# UBC-Thunderbots_PCB_Power__power-v2_2_pc.net
KiCad netlist of a schematic drawn in Altium Designer
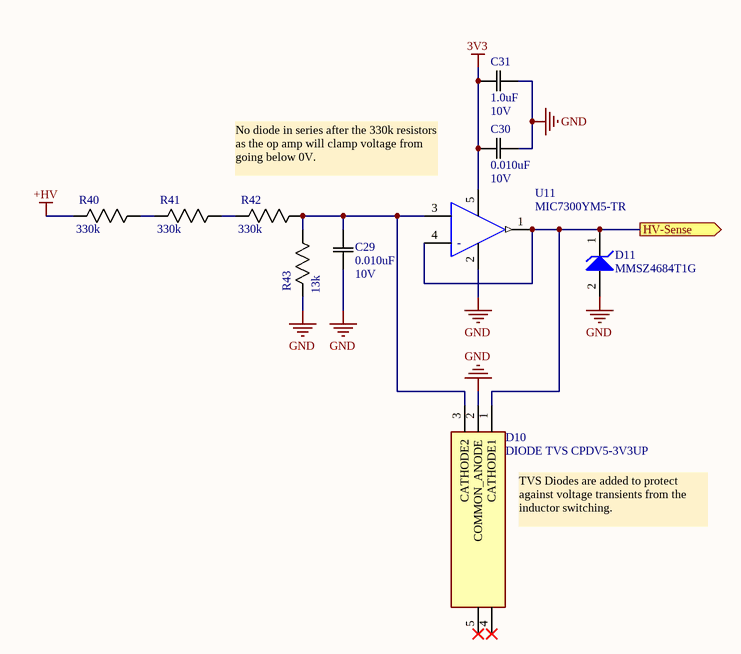
[diagram p0: UBC-Thunderbots_PCB_Power__power-v2.2_pcb__HV-Measurement.SchDoc]

(export (version "E")
  (design (tool "Eeschema 10.0.6"))
  (components
    (comp (ref "C29")
      (value "0.010uF")
      (footprint "0603")
      (description "CAP CER 0.010UF 10V X7R 0603")
      (fields (field (name "TOLERANCE") "10%") (field (name "RATING") "10V"))
      (libsource (lib "AltiumLibraries") (part "CAP 0.010uF 16V"))
    )
    (comp (ref "C30")
      (value "0.010uF")
      (footprint "0603")
      (description "CAP CER 0.010UF 10V X7R 0603")
      (fields (field (name "TOLERANCE") "10%") (field (name "RATING") "10V"))
      (libsource (lib "AltiumLibraries") (part "CAP 0.010uF 16V"))
    )
    (comp (ref "C31")
      (value "1.0uF")
      (footprint "0603")
      (description "CAP CER 1.0UF 10V X5R 0603")
      (fields (field (name "TOLERANCE") "10%") (field (name "RATING") "10V"))
      (libsource (lib "AltiumLibraries") (part "CAP 1.0uF 16V"))
    )
    (comp (ref "D10")
      (value "DIODE TVS CPDV5-3V3UP")
      (footprint "SOT65P230X110-5N")
      (description "TVS Diode Bidirectional Vbr = 3.5V, Working Voltage = 3.3V")
      (fields
        (field (name "MANUFACTURER_PART_NUMBER") "CPDV5-3V3UP")
        (field (name "MOUSER PART NUMBER") "750-CPDV5-3V3UP")
      )
      (libsource (lib "AltiumLibraries") (part "DIODE TVS CPDV5-3V3UP"))
    )
    (comp (ref "D11")
      (value "MMSZ4684T1G")
      (footprint "ONSC-SOD-123-2-425-04_V")
      (description "Zener 3V3 Voltage Regulator, 500 mW, 2-Pin SOD-123, Pb-Free, Tape and Reel")
      (fields (field (name "MANUFACTURER") "On Semiconductor"))
      (libsource (lib "AltiumLibraries") (part "DIODE ZENER 3.3 500mW"))
    )
    (comp (ref "R40")
      (value "330k")
      (footprint "0805")
      (description "RES SMD 330K OHM 5% 1/8W 0805")
      (fields (field (name "TOLERANCE") "5%"))
      (libsource (lib "") (part "RES 330k 1/8W - 5%_1"))
    )
    (comp (ref "R41")
      (value "330k")
      (footprint "0805")
      (description "CRCW0805330KFKEA")
      (fields (field (name "TOLERANCE") "5%"))
      (libsource (lib "AltiumLibraries") (part "RES 330k 1/8W - 5%"))
    )
    (comp (ref "R42")
      (value "330k")
      (footprint "0805")
      (description "RES SMD 330K OHM 5% 1/8W 0805")
      (fields (field (name "TOLERANCE") "5%"))
      (libsource (lib "AltiumLibraries") (part "RES 330k 1/8W - 5%"))
    )
    (comp (ref "R43")
      (value "13k")
      (footprint "0805")
      (description "RES SMD 13K OHM 5% 1/8W 0805")
      (fields (field (name "TOLERANCE") "5%"))
      (libsource (lib "AltiumLibraries") (part "RES 13k 1/8W"))
    )
    (comp (ref "U11")
      (value "MIC7300YM5-TR")
      (footprint "FP-SOT23-5LD-PL-1-IPC_A")
      (description "IC OPAMP GP 1 CIRCUIT SOT23-5")
      (fields
        (field (name "OCTOPART") "https://octopart.com/mic7300ym5-tr-microchip-66803593")
        (field (name "MANUFACTURER") "Microchip")
      )
      (libsource (lib "AltiumLibraries") (part "OP AMP MIC7300YM5-TR"))
    )
  )
  (nets
    (net (code "1") (name "+HV") (class "Default")
      (node (ref "R40") (pin "2") (pinfunction "R2_2") (pintype "passive"))
    )
    (net (code "2") (name "/HV-Sense") (class "Default")
      (node (ref "D10") (pin "1") (pinfunction "CATHODE1_1") (pintype "passive"))
      (node (ref "D11") (pin "1") (pinfunction "K_1") (pintype "passive"))
      (node (ref "U11") (pin "1") (pinfunction "OUT_1") (pintype "output"))
      (node (ref "U11") (pin "4") (pinfunction "IN-_4") (pintype "tri_state"))
    )
    (net (code "3") (name "3V3") (class "Default")
      (node (ref "C30") (pin "1") (pinfunction "C1_1") (pintype "passive"))
      (node (ref "C31") (pin "2") (pinfunction "C2_2") (pintype "passive"))
      (node (ref "U11") (pin "5") (pinfunction "V+_5") (pintype "power_in"))
    )
    (net (code "4") (name "GND") (class "Default")
      (node (ref "C29") (pin "1") (pinfunction "C1_1") (pintype "passive"))
      (node (ref "C30") (pin "2") (pinfunction "C2_2") (pintype "passive"))
      (node (ref "C31") (pin "1") (pinfunction "C1_1") (pintype "passive"))
      (node (ref "D10") (pin "2") (pinfunction "COMMON_ANODE_2") (pintype "passive"))
      (node (ref "D11") (pin "2") (pinfunction "A_2") (pintype "passive"))
      (node (ref "R43") (pin "2") (pinfunction "R2_2") (pintype "passive"))
      (node (ref "U11") (pin "2") (pinfunction "V-_2") (pintype "power_in"))
    )
    (net (code "5") (name "Net-(C29-C2)") (class "Default")
      (node (ref "C29") (pin "2") (pinfunction "C2_2") (pintype "passive"))
      (node (ref "D10") (pin "3") (pinfunction "CATHODE2_3") (pintype "passive"))
      (node (ref "R42") (pin "1") (pinfunction "R1_1") (pintype "passive"))
      (node (ref "R43") (pin "1") (pinfunction "R1_1") (pintype "passive"))
      (node (ref "U11") (pin "3") (pinfunction "IN+_3") (pintype "tri_state"))
    )
    (net (code "6") (name "Net-(R40-R1)") (class "Default")
      (node (ref "R40") (pin "1") (pinfunction "R1_1") (pintype "passive"))
      (node (ref "R41") (pin "2") (pinfunction "R2_2") (pintype "passive"))
    )
    (net (code "7") (name "Net-(R41-R1)") (class "Default")
      (node (ref "R41") (pin "1") (pinfunction "R1_1") (pintype "passive"))
      (node (ref "R42") (pin "2") (pinfunction "R2_2") (pintype "passive"))
    )
    (net (code "8") (name "unconnected-(D10-CATHODE3-Pad4)") (class "Default")
      (node (ref "D10") (pin "4") (pinfunction "CATHODE3_4") (pintype "passive+no_connect"))
    )
    (net (code "9") (name "unconnected-(D10-CATHODE4-Pad5)") (class "Default")
      (node (ref "D10") (pin "5") (pinfunction "CATHODE4_5") (pintype "passive+no_connect"))
    )
  )
)
